# Encoder_v1.net
KiCad netlist of a schematic drawn in EAGLE
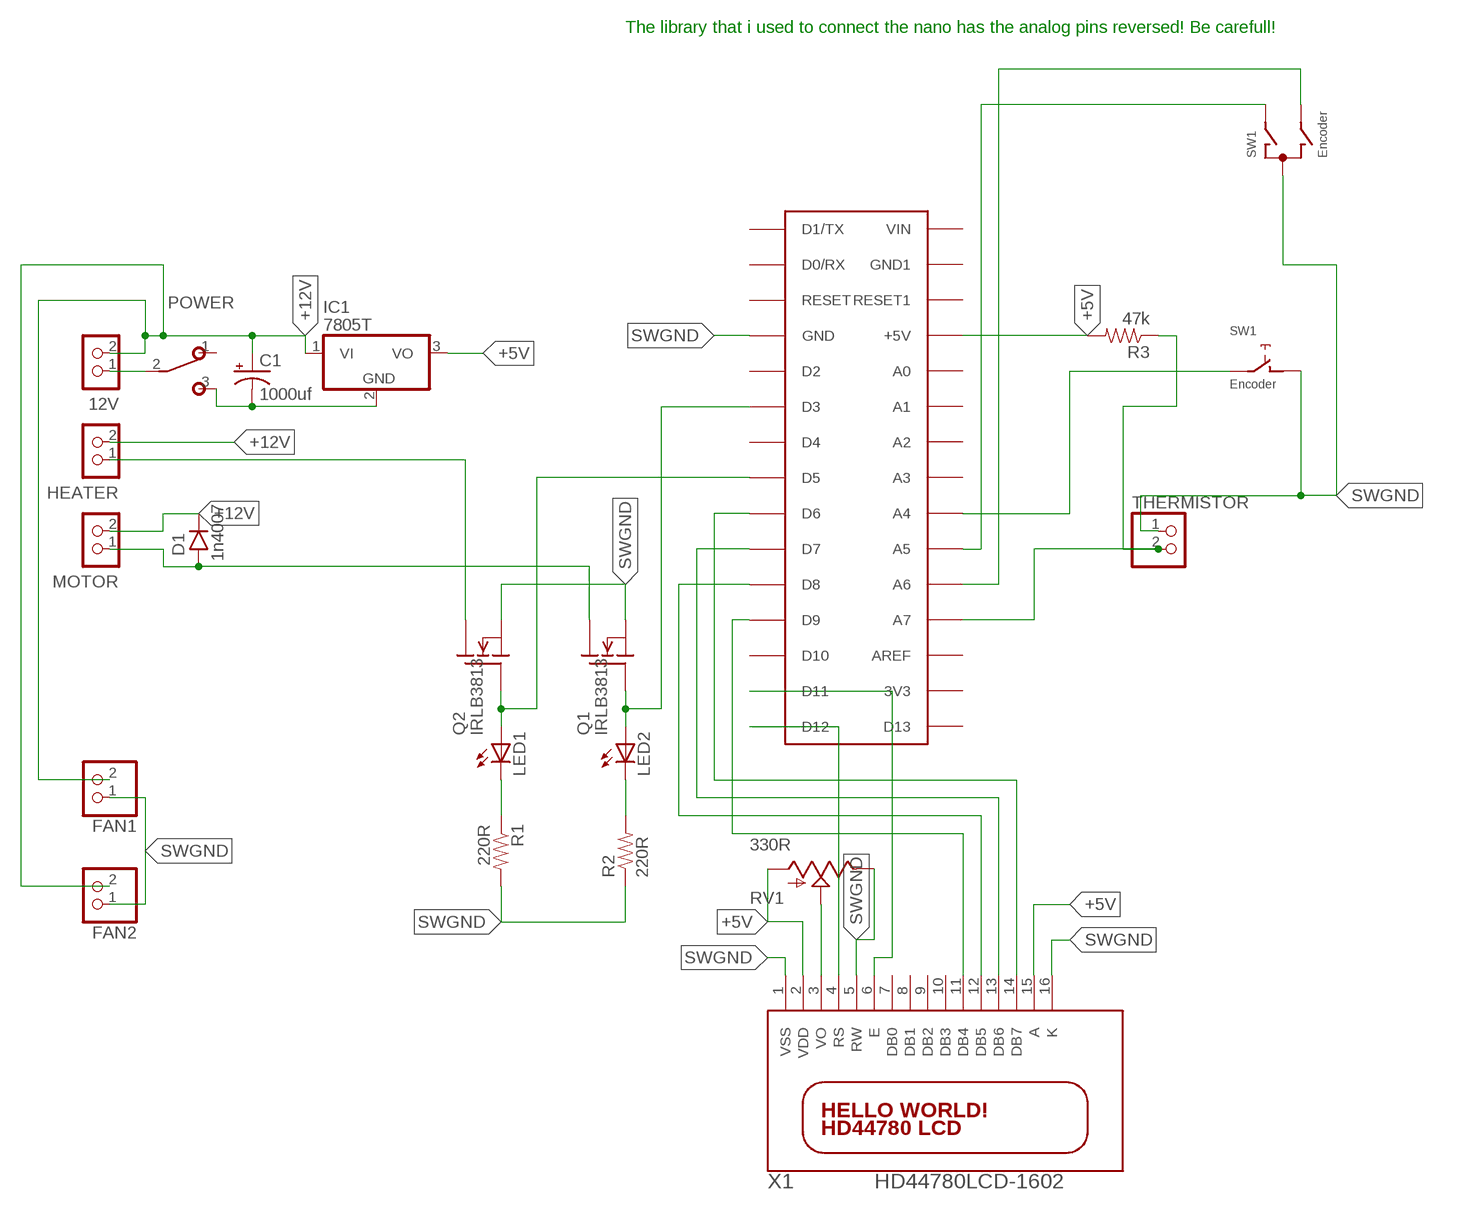
[diagram p0: schematic, sheet 1]

(export (version "E")
  (design (tool "Eeschema 10.0.6"))
  (components
    (comp (ref "12V")
      (value "CON_TERMINAL_BLOCK_02-5MM")
      (footprint "eagle-import:TERMINAL_BLOCK_2P_5")
      (libsource (lib "eagle-import") (part "CON_TERMINAL_BLOCK_02-5MM"))
    )
    (comp (ref "A01")
      (value "ARDUINO NANO")
      (footprint "eagle-import:PDIP-32")
      (libsource (lib "eagle-import") (part "ARDUINONANO"))
    )
    (comp (ref "C1")
      (value "1000uf")
      (footprint "eagle-import:CPOL-RADIAL-1000UF-25V")
      (libsource (lib "eagle-import") (part "CAP_POLPTH4"))
    )
    (comp (ref "D1")
      (value "1n4007")
      (footprint "eagle-import:DO41-4")
      (libsource (lib "eagle-import") (part "1N400X.4"))
    )
    (comp (ref "FAN1")
      (value "PINHD-1X2")
      (footprint "eagle-import:1X02")
      (libsource (lib "eagle-import") (part "PINHD-1X2"))
    )
    (comp (ref "FAN2")
      (value "PINHD-1X2")
      (footprint "eagle-import:1X02")
      (libsource (lib "eagle-import") (part "PINHD-1X2"))
    )
    (comp (ref "HEATER")
      (value "CON_TERMINAL_BLOCK_02-5MM")
      (footprint "eagle-import:TERMINAL_BLOCK_2P_5")
      (libsource (lib "eagle-import") (part "CON_TERMINAL_BLOCK_02-5MM"))
    )
    (comp (ref "IC1")
      (value "7805T")
      (footprint "eagle-import:TO220H")
      (libsource (lib "eagle-import") (part "78T05"))
    )
    (comp (ref "LED1")
      (value "LED5MM")
      (footprint "eagle-import:LED5MM")
      (libsource (lib "eagle-import") (part "LED5MM"))
    )
    (comp (ref "LED2")
      (value "LED5MM")
      (footprint "eagle-import:LED5MM")
      (libsource (lib "eagle-import") (part "LED5MM"))
    )
    (comp (ref "MOTOR")
      (value "CON_TERMINAL_BLOCK_02-5MM")
      (footprint "eagle-import:TERMINAL_BLOCK_2P_5")
      (libsource (lib "eagle-import") (part "CON_TERMINAL_BLOCK_02-5MM"))
    )
    (comp (ref "POWER")
      (value "SPDT")
      (footprint "eagle-import:M9040P")
      (libsource (lib "eagle-import") (part "SPDT"))
    )
    (comp (ref "Q1")
      (value "IRLB3813")
      (footprint "eagle-import:TO220")
      (libsource (lib "eagle-import") (part "IRF620"))
    )
    (comp (ref "Q2")
      (value "IRLB3813")
      (footprint "eagle-import:TO220")
      (libsource (lib "eagle-import") (part "IRF620"))
    )
    (comp (ref "R1")
      (value "220R")
      (footprint "eagle-import:AXIAL-0.4")
      (libsource (lib "eagle-import") (part "RESISTORPTH-1/4W"))
    )
    (comp (ref "R2")
      (value "220R")
      (footprint "eagle-import:AXIAL-0.4")
      (libsource (lib "eagle-import") (part "RESISTORPTH-1/4W"))
    )
    (comp (ref "R3")
      (value "47k")
      (footprint "eagle-import:AXIAL-0.4")
      (libsource (lib "eagle-import") (part "RESISTORPTH-1/4W"))
    )
    (comp (ref "RV1")
      (value "330R")
      (footprint "eagle-import:TRIM_POT")
      (libsource (lib "eagle-import") (part "POTTRIM"))
    )
    (comp (ref "SW1")
      (value "Encoder")
      (footprint "eagle-import:ALPS_EC12E_SW")
      (fields (field (name "MPN") "EC12E2424407"))
      (libsource (lib "eagle-import") (part "EC12E_SW"))
    )
    (comp (ref "THERMISTOR")
      (value "PINHD-1X2")
      (footprint "eagle-import:1X02")
      (libsource (lib "eagle-import") (part "PINHD-1X2"))
    )
    (comp (ref "X1")
      (value "HD44780LCD-1602")
      (footprint "eagle-import:LCD1602")
      (libsource (lib "eagle-import") (part "HD44780LCD-1602"))
    )
  )
  (nets
    (net (code "1") (name "+5V") (class "Default")
      (node (ref "A01") (pin "+5V") (pinfunction "+5V_+5V") (pintype "bidirectional"))
      (node (ref "IC1") (pin "3") (pinfunction "VO_3") (pintype "passive"))
      (node (ref "R3") (pin "P$2") (pinfunction "2_P$2") (pintype "passive"))
      (node (ref "RV1") (pin "3") (pinfunction "A_3") (pintype "passive"))
      (node (ref "X1") (pin "15") (pinfunction "A_15") (pintype "input"))
      (node (ref "X1") (pin "2") (pinfunction "VDD_2") (pintype "power_in"))
    )
    (net (code "2") (name "+12V") (class "Default")
      (node (ref "12V") (pin "2") (pinfunction "2_2") (pintype "passive"))
      (node (ref "C1") (pin "1") (pinfunction "+_1") (pintype "passive"))
      (node (ref "D1") (pin "C") (pinfunction "C_C") (pintype "passive"))
      (node (ref "FAN1") (pin "2") (pinfunction "2_2") (pintype "passive"))
      (node (ref "FAN2") (pin "2") (pinfunction "2_2") (pintype "passive"))
      (node (ref "HEATER") (pin "2") (pinfunction "2_2") (pintype "passive"))
      (node (ref "IC1") (pin "1") (pinfunction "VI_1") (pintype "input"))
      (node (ref "MOTOR") (pin "2") (pinfunction "2_2") (pintype "passive"))
    )
    (net (code "3") (name "Net-(A01-PadA5)") (class "Default")
      (node (ref "A01") (pin "A5") (pinfunction "A5_A5") (pintype "bidirectional"))
      (node (ref "SW1") (pin "A") (pinfunction "A_A") (pintype "passive"))
    )
    (net (code "4") (name "Net-(A01-PadA6)") (class "Default")
      (node (ref "A01") (pin "A6") (pinfunction "A6_A6") (pintype "bidirectional"))
      (node (ref "SW1") (pin "B") (pinfunction "B_B") (pintype "passive"))
    )
    (net (code "5") (name "Net-(LED1-C)") (class "Default")
      (node (ref "LED1") (pin "K") (pinfunction "C_K") (pintype "passive"))
      (node (ref "R1") (pin "P$1") (pinfunction "1_P$1") (pintype "passive"))
    )
    (net (code "6") (name "Net-(LED2-C)") (class "Default")
      (node (ref "LED2") (pin "K") (pinfunction "C_K") (pintype "passive"))
      (node (ref "R2") (pin "P$2") (pinfunction "2_P$2") (pintype "passive"))
    )
    (net (code "7") (name "Net-(POWER-P)") (class "Default")
      (node (ref "12V") (pin "1") (pinfunction "1_1") (pintype "passive"))
      (node (ref "POWER") (pin "2") (pinfunction "P_2") (pintype "passive"))
    )
    (net (code "8") (name "Net-(Q1-D)") (class "Default")
      (node (ref "D1") (pin "A") (pinfunction "A_A") (pintype "passive"))
      (node (ref "MOTOR") (pin "1") (pinfunction "1_1") (pintype "passive"))
      (node (ref "Q1") (pin "2") (pinfunction "D_2") (pintype "passive"))
    )
    (net (code "9") (name "Net-(Q1-G)") (class "Default")
      (node (ref "A01") (pin "D3") (pinfunction "D3_D3") (pintype "bidirectional"))
      (node (ref "LED2") (pin "A") (pinfunction "A_A") (pintype "passive"))
      (node (ref "Q1") (pin "1") (pinfunction "G_1") (pintype "passive"))
    )
    (net (code "10") (name "Net-(Q2-D)") (class "Default")
      (node (ref "HEATER") (pin "1") (pinfunction "1_1") (pintype "passive"))
      (node (ref "Q2") (pin "2") (pinfunction "D_2") (pintype "passive"))
    )
    (net (code "11") (name "Net-(Q2-G)") (class "Default")
      (node (ref "A01") (pin "D5") (pinfunction "D5_D5") (pintype "bidirectional"))
      (node (ref "LED1") (pin "A") (pinfunction "A_A") (pintype "passive"))
      (node (ref "Q2") (pin "1") (pinfunction "G_1") (pintype "passive"))
    )
    (net (code "12") (name "Net-(R3-1)") (class "Default")
      (node (ref "A01") (pin "A7") (pinfunction "A7_A7") (pintype "bidirectional"))
      (node (ref "R3") (pin "P$1") (pinfunction "1_P$1") (pintype "passive"))
      (node (ref "THERMISTOR") (pin "2") (pinfunction "2_2") (pintype "passive"))
    )
    (net (code "13") (name "Net-(RV1-S)") (class "Default")
      (node (ref "RV1") (pin "1") (pinfunction "S_1") (pintype "passive"))
      (node (ref "X1") (pin "3") (pinfunction "VO_3") (pintype "input"))
    )
    (net (code "14") (name "Net-(SW1B-2)") (class "Default")
      (node (ref "A01") (pin "A4") (pinfunction "A4_A4") (pintype "bidirectional"))
      (node (ref "SW1") (pin "E") (pinfunction "2_E") (pintype "passive"))
    )
    (net (code "15") (name "Net-(X1-DB4)") (class "Default")
      (node (ref "A01") (pin "D9") (pinfunction "D9_D9") (pintype "bidirectional"))
      (node (ref "X1") (pin "11") (pinfunction "DB4_11") (pintype "bidirectional"))
    )
    (net (code "16") (name "Net-(X1-DB5)") (class "Default")
      (node (ref "A01") (pin "D8") (pinfunction "D8_D8") (pintype "bidirectional"))
      (node (ref "X1") (pin "12") (pinfunction "DB5_12") (pintype "bidirectional"))
    )
    (net (code "17") (name "Net-(X1-DB6)") (class "Default")
      (node (ref "A01") (pin "D7") (pinfunction "D7_D7") (pintype "bidirectional"))
      (node (ref "X1") (pin "13") (pinfunction "DB6_13") (pintype "bidirectional"))
    )
    (net (code "18") (name "Net-(X1-DB7)") (class "Default")
      (node (ref "A01") (pin "D6") (pinfunction "D6_D6") (pintype "bidirectional"))
      (node (ref "X1") (pin "14") (pinfunction "DB7_14") (pintype "bidirectional"))
    )
    (net (code "19") (name "Net-(X1-E)") (class "Default")
      (node (ref "A01") (pin "D11") (pinfunction "D11_D11") (pintype "bidirectional"))
      (node (ref "X1") (pin "6") (pinfunction "E_6") (pintype "input"))
    )
    (net (code "20") (name "Net-(X1-RS)") (class "Default")
      (node (ref "A01") (pin "D12") (pinfunction "D12_D12") (pintype "bidirectional"))
      (node (ref "X1") (pin "4") (pinfunction "RS_4") (pintype "input"))
    )
    (net (code "21") (name "SWGND") (class "Default")
      (node (ref "A01") (pin "GND") (pinfunction "GND_GND") (pintype "bidirectional"))
      (node (ref "C1") (pin "2") (pinfunction "-_2") (pintype "passive"))
      (node (ref "FAN1") (pin "1") (pinfunction "1_1") (pintype "passive"))
      (node (ref "FAN2") (pin "1") (pinfunction "1_1") (pintype "passive"))
      (node (ref "IC1") (pin "2") (pinfunction "GND_2") (pintype "passive"))
      (node (ref "POWER") (pin "3") (pinfunction "S_3") (pintype "passive"))
      (node (ref "Q1") (pin "3") (pinfunction "S_3") (pintype "passive"))
      (node (ref "Q2") (pin "3") (pinfunction "S_3") (pintype "passive"))
      (node (ref "R1") (pin "P$2") (pinfunction "2_P$2") (pintype "passive"))
      (node (ref "R2") (pin "P$1") (pinfunction "1_P$1") (pintype "passive"))
      (node (ref "RV1") (pin "2") (pinfunction "E_2") (pintype "passive"))
      (node (ref "SW1") (pin "C") (pinfunction "C_C") (pintype "passive"))
      (node (ref "SW1") (pin "D") (pinfunction "1_D") (pintype "passive"))
      (node (ref "THERMISTOR") (pin "1") (pinfunction "1_1") (pintype "passive"))
      (node (ref "X1") (pin "1") (pinfunction "VSS_1") (pintype "power_in"))
      (node (ref "X1") (pin "16") (pinfunction "K_16") (pintype "input"))
      (node (ref "X1") (pin "5") (pinfunction "RW_5") (pintype "input"))
    )
    (net (code "22") (name "unconnected-(A01-Pad3V3)") (class "Default")
      (node (ref "A01") (pin "3V3") (pinfunction "3V3_3V3") (pintype "bidirectional"))
    )
    (net (code "23") (name "unconnected-(A01-PadA0)") (class "Default")
      (node (ref "A01") (pin "A0") (pinfunction "A0_A0") (pintype "bidirectional"))
    )
    (net (code "24") (name "unconnected-(A01-PadA1)") (class "Default")
      (node (ref "A01") (pin "A1") (pinfunction "A1_A1") (pintype "bidirectional"))
    )
    (net (code "25") (name "unconnected-(A01-PadA2)") (class "Default")
      (node (ref "A01") (pin "A2") (pinfunction "A2_A2") (pintype "bidirectional"))
    )
    (net (code "26") (name "unconnected-(A01-PadA3)") (class "Default")
      (node (ref "A01") (pin "A3") (pinfunction "A3_A3") (pintype "bidirectional"))
    )
    (net (code "27") (name "unconnected-(A01-PadAREF)") (class "Default")
      (node (ref "A01") (pin "AREF") (pinfunction "AREF_AREF") (pintype "bidirectional"))
    )
    (net (code "28") (name "unconnected-(A01-PadD0{slash}RX)") (class "Default")
      (node (ref "A01") (pin "D0/RX") (pinfunction "D0/RX_D0/RX") (pintype "bidirectional"))
    )
    (net (code "29") (name "unconnected-(A01-PadD1{slash}TX)") (class "Default")
      (node (ref "A01") (pin "D1/TX") (pinfunction "D1/TX_D1/TX") (pintype "bidirectional"))
    )
    (net (code "30") (name "unconnected-(A01-PadD2)") (class "Default")
      (node (ref "A01") (pin "D2") (pinfunction "D2_D2") (pintype "bidirectional"))
    )
    (net (code "31") (name "unconnected-(A01-PadD4)") (class "Default")
      (node (ref "A01") (pin "D4") (pinfunction "D4_D4") (pintype "bidirectional"))
    )
    (net (code "32") (name "unconnected-(A01-PadD10)") (class "Default")
      (node (ref "A01") (pin "D10") (pinfunction "D10_D10") (pintype "bidirectional"))
    )
    (net (code "33") (name "unconnected-(A01-PadD13)") (class "Default")
      (node (ref "A01") (pin "D13") (pinfunction "D13_D13") (pintype "bidirectional"))
    )
    (net (code "34") (name "unconnected-(A01-PadGND1)") (class "Default")
      (node (ref "A01") (pin "GND1") (pinfunction "GND1_GND1") (pintype "bidirectional"))
    )
    (net (code "35") (name "unconnected-(A01-PadRESET)") (class "Default")
      (node (ref "A01") (pin "RESET") (pinfunction "RESET_RESET") (pintype "bidirectional"))
    )
    (net (code "36") (name "unconnected-(A01-PadRESET1)") (class "Default")
      (node (ref "A01") (pin "RESET1") (pinfunction "RESET1_RESET1") (pintype "bidirectional"))
    )
    (net (code "37") (name "unconnected-(A01-PadVIN)") (class "Default")
      (node (ref "A01") (pin "VIN") (pinfunction "VIN_VIN") (pintype "bidirectional"))
    )
    (net (code "38") (name "unconnected-(POWER-O-Pad1)") (class "Default")
      (node (ref "POWER") (pin "1") (pinfunction "O_1") (pintype "passive"))
    )
    (net (code "39") (name "unconnected-(X1-DB0-Pad7)") (class "Default")
      (node (ref "X1") (pin "7") (pinfunction "DB0_7") (pintype "bidirectional"))
    )
    (net (code "40") (name "unconnected-(X1-DB1-Pad8)") (class "Default")
      (node (ref "X1") (pin "8") (pinfunction "DB1_8") (pintype "bidirectional"))
    )
    (net (code "41") (name "unconnected-(X1-DB2-Pad9)") (class "Default")
      (node (ref "X1") (pin "9") (pinfunction "DB2_9") (pintype "bidirectional"))
    )
    (net (code "42") (name "unconnected-(X1-DB3-Pad10)") (class "Default")
      (node (ref "X1") (pin "10") (pinfunction "DB3_10") (pintype "bidirectional"))
    )
  )
)
